# ME433Schematic.net
KiCad netlist of a schematic drawn in EAGLE
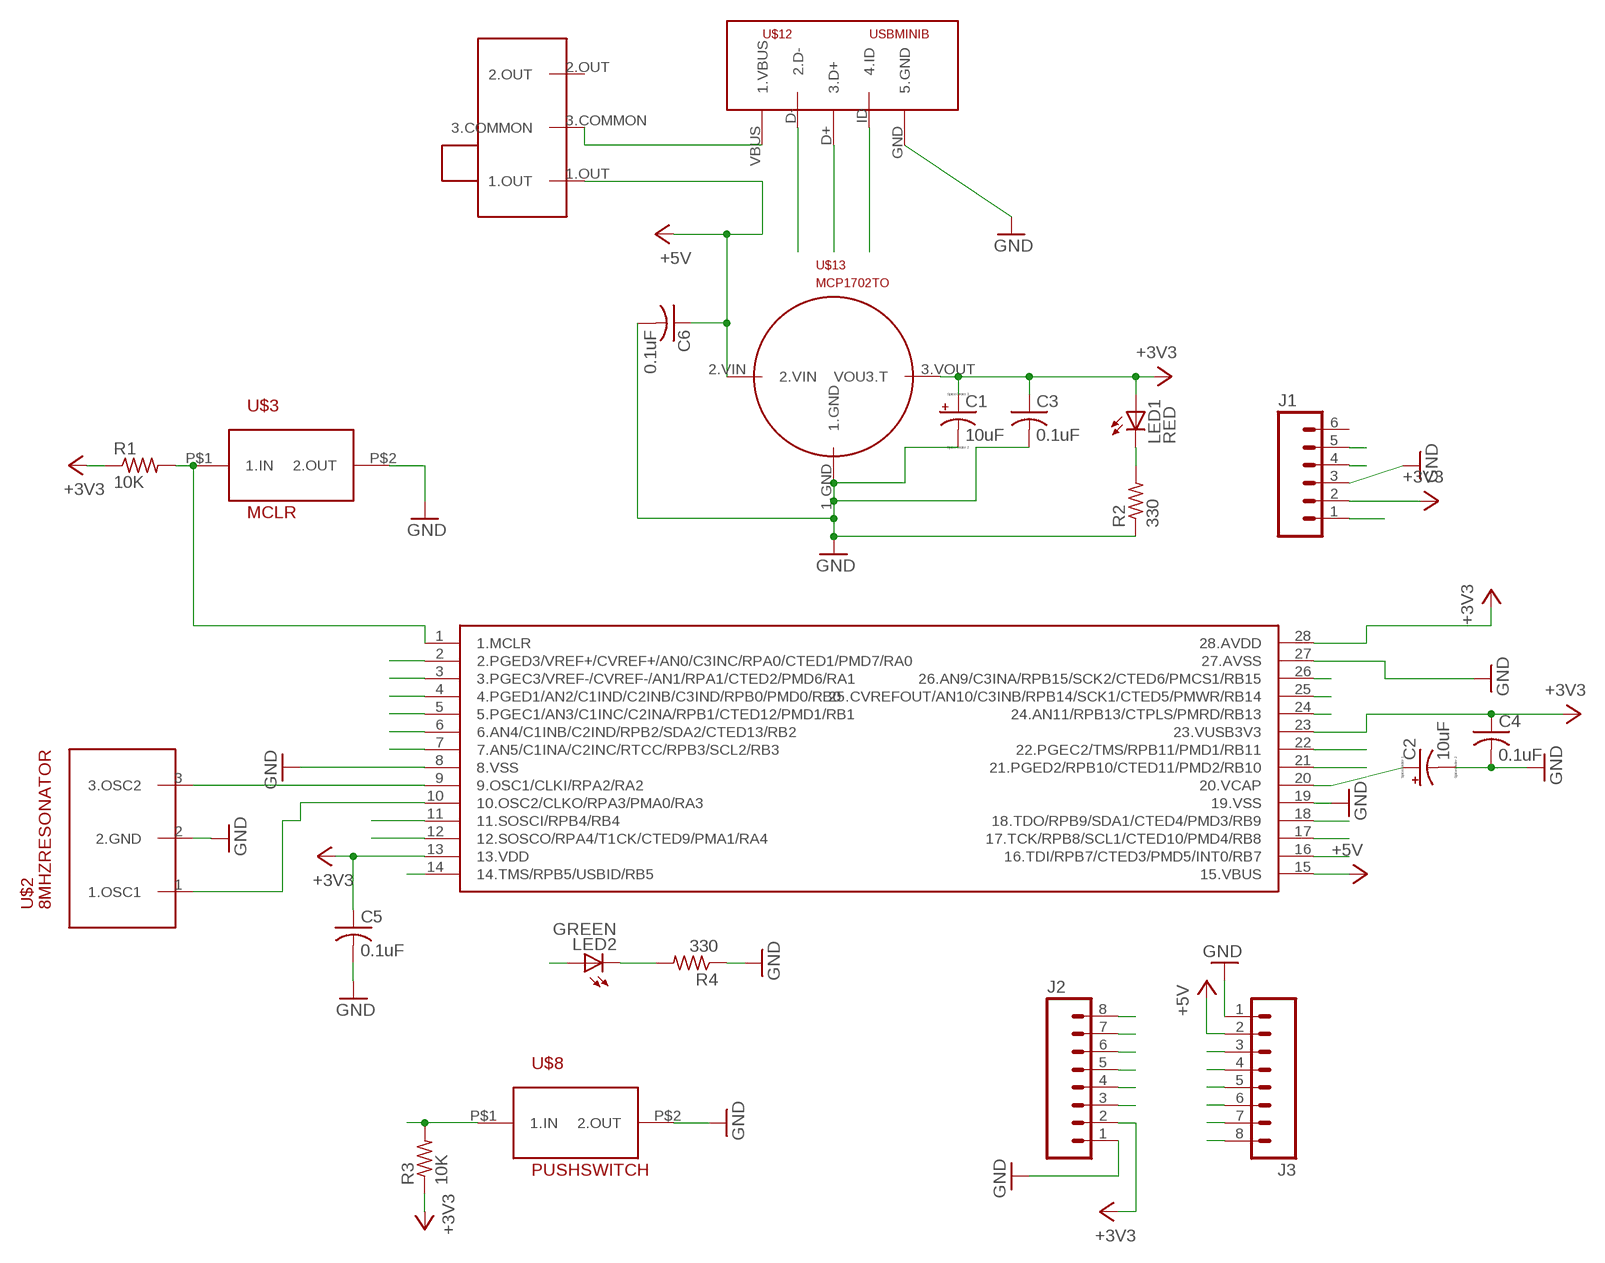
[diagram p0: schematic, sheet 1]

(export (version "E")
  (design (tool "Eeschema 10.0.6"))
  (components
    (comp (ref "C1")
      (value "10uF")
      (footprint "eagle-import:B45181B")
      (libsource (lib "eagle-import") (part "CPOL-USB45181B"))
    )
    (comp (ref "C2")
      (value "10uF")
      (footprint "eagle-import:B45181B")
      (libsource (lib "eagle-import") (part "CPOL-USB45181B"))
    )
    (comp (ref "C3")
      (value "0.1uF")
      (footprint "eagle-import:C025-025X050")
      (libsource (lib "eagle-import") (part "C-US025-025X050"))
    )
    (comp (ref "C4")
      (value "0.1uF")
      (footprint "eagle-import:C025-025X050")
      (libsource (lib "eagle-import") (part "C-US025-025X050"))
    )
    (comp (ref "C5")
      (value "0.1uF")
      (footprint "eagle-import:C025-025X050")
      (libsource (lib "eagle-import") (part "C-US025-025X050"))
    )
    (comp (ref "C6")
      (value "0.1uF")
      (footprint "eagle-import:C025-025X050")
      (libsource (lib "eagle-import") (part "C-US025-025X050"))
    )
    (comp (ref "J1")
      (value "M06SILK_FEMALE_PTH")
      (footprint "eagle-import:1X06")
      (libsource (lib "eagle-import") (part "M06SILK_FEMALE_PTH"))
    )
    (comp (ref "J2")
      (value "M08")
      (footprint "eagle-import:1X08_ROUND")
      (libsource (lib "eagle-import") (part "M08"))
    )
    (comp (ref "J3")
      (value "M08")
      (footprint "eagle-import:1X08_ROUND")
      (libsource (lib "eagle-import") (part "M08"))
    )
    (comp (ref "LED1")
      (value "RED")
      (footprint "eagle-import:LED3MM")
      (libsource (lib "eagle-import") (part "LED3MM"))
    )
    (comp (ref "LED2")
      (value "GREEN")
      (footprint "eagle-import:LED3MM")
      (libsource (lib "eagle-import") (part "LED3MM"))
    )
    (comp (ref "R1")
      (value "10K")
      (footprint "eagle-import:0207_10")
      (libsource (lib "eagle-import") (part "R-US_0207/10"))
    )
    (comp (ref "R2")
      (value "330")
      (footprint "eagle-import:0207_10")
      (libsource (lib "eagle-import") (part "R-US_0207/10"))
    )
    (comp (ref "R3")
      (value "10K")
      (footprint "eagle-import:0207_10")
      (libsource (lib "eagle-import") (part "R-US_0207/10"))
    )
    (comp (ref "R4")
      (value "330")
      (footprint "eagle-import:0207_10")
      (libsource (lib "eagle-import") (part "R-US_0207/10"))
    )
    (comp (ref "U$1")
      (value "PIC32MX250F128B")
      (footprint "eagle-import:DIL28-3")
      (libsource (lib "eagle-import") (part "PIC32MX250F128B"))
    )
    (comp (ref "U$2")
      (value "8MHZRESONATOR")
      (footprint "eagle-import:1X03")
      (libsource (lib "eagle-import") (part "8MHZRESONATOR"))
    )
    (comp (ref "U$3")
      (value "MCLR")
      (footprint "eagle-import:SWITCH")
      (libsource (lib "eagle-import") (part "PUSHSWITCH"))
    )
    (comp (ref "U$8")
      (value "PUSHSWITCH")
      (footprint "eagle-import:SWITCH")
      (libsource (lib "eagle-import") (part "PUSHSWITCH"))
    )
    (comp (ref "U$12")
      (value "USBMINIB")
      (footprint "eagle-import:USB-MB-H")
      (libsource (lib "eagle-import") (part "USBMINIB"))
    )
    (comp (ref "U$13")
      (value "MCP1702TO")
      (footprint "eagle-import:TO92")
      (libsource (lib "eagle-import") (part "MCP1702TO"))
    )
    (comp (ref "U$18")
      (value "SLIDESWITCH")
      (footprint "eagle-import:SPDTSLIDE")
      (libsource (lib "eagle-import") (part "SLIDESWITCH"))
    )
  )
  (nets
    (net (code "1") (name "+3V3") (class "Default")
      (node (ref "C1") (pin "+") (pinfunction "+_+") (pintype "passive"))
      (node (ref "C3") (pin "1") (pinfunction "1_1") (pintype "passive"))
      (node (ref "C4") (pin "1") (pinfunction "1_1") (pintype "passive"))
      (node (ref "C5") (pin "1") (pinfunction "1_1") (pintype "passive"))
      (node (ref "J1") (pin "2") (pinfunction "2_2") (pintype "passive"))
      (node (ref "J2") (pin "2") (pinfunction "2_2") (pintype "passive"))
      (node (ref "LED1") (pin "A") (pinfunction "1.+_A") (pintype "passive"))
      (node (ref "R1") (pin "1") (pinfunction "1_1") (pintype "passive"))
      (node (ref "R3") (pin "1") (pinfunction "1_1") (pintype "passive"))
      (node (ref "U$1") (pin "13") (pinfunction "13.VDD_13") (pintype "bidirectional"))
      (node (ref "U$1") (pin "23") (pinfunction "23.VUSB3V3_23") (pintype "bidirectional"))
      (node (ref "U$1") (pin "28") (pinfunction "28.AVDD_28") (pintype "bidirectional"))
      (node (ref "U$13") (pin "3.VOUT") (pinfunction "VOU3.T_3.VOUT") (pintype "bidirectional"))
    )
    (net (code "2") (name "+5V") (class "Default")
      (node (ref "C6") (pin "1") (pinfunction "1_1") (pintype "passive"))
      (node (ref "J3") (pin "2") (pinfunction "2_2") (pintype "passive"))
      (node (ref "U$1") (pin "15") (pinfunction "15.VBUS_15") (pintype "bidirectional"))
      (node (ref "U$13") (pin "2.VIN") (pinfunction "2.VIN_2.VIN") (pintype "bidirectional"))
      (node (ref "U$18") (pin "1.OUT") (pinfunction "1.OUT_1.OUT") (pintype "bidirectional"))
    )
    (net (code "3") (name "/A0") (class "Default")
      (node (ref "J2") (pin "8") (pinfunction "8_8") (pintype "passive"))
      (node (ref "U$1") (pin "2") (pinfunction "2.PGED3/VREF+/CVREF+/AN0/C3INC/RPA0/CTED1/PMD7/RA0_2") (pintype "bidirectional"))
    )
    (net (code "4") (name "/A1") (class "Default")
      (node (ref "J2") (pin "7") (pinfunction "7_7") (pintype "passive"))
      (node (ref "U$1") (pin "3") (pinfunction "3.PGEC3/VREF-/CVREF-/AN1/RPA1/CTED2/PMD6/RA1_3") (pintype "bidirectional"))
    )
    (net (code "5") (name "/A4") (class "Default")
      (node (ref "J2") (pin "3") (pinfunction "3_3") (pintype "passive"))
      (node (ref "LED2") (pin "A") (pinfunction "1.+_A") (pintype "passive"))
      (node (ref "U$1") (pin "12") (pinfunction "12.SOSCO/RPA4/T1CK/CTED9/PMA1/RA4_12") (pintype "bidirectional"))
    )
    (net (code "6") (name "/B2") (class "Default")
      (node (ref "J2") (pin "6") (pinfunction "6_6") (pintype "passive"))
      (node (ref "U$1") (pin "6") (pinfunction "6.AN4/C1INB/C2IND/RPB2/SDA2/CTED13/RB2_6") (pintype "bidirectional"))
    )
    (net (code "7") (name "/B3") (class "Default")
      (node (ref "J2") (pin "5") (pinfunction "5_5") (pintype "passive"))
      (node (ref "U$1") (pin "7") (pinfunction "7.AN5/C1INA/C2INC/RTCC/RPB3/SCL2/RB3_7") (pintype "bidirectional"))
    )
    (net (code "8") (name "/B4") (class "Default")
      (node (ref "J2") (pin "4") (pinfunction "4_4") (pintype "passive"))
      (node (ref "R3") (pin "2") (pinfunction "2_2") (pintype "passive"))
      (node (ref "U$1") (pin "11") (pinfunction "11.SOSCI/RPB4/RB4_11") (pintype "bidirectional"))
      (node (ref "U$8") (pin "P$1") (pinfunction "1.IN_P$1") (pintype "bidirectional"))
    )
    (net (code "9") (name "/B7") (class "Default")
      (node (ref "J3") (pin "3") (pinfunction "3_3") (pintype "passive"))
      (node (ref "U$1") (pin "16") (pinfunction "16.TDI/RPB7/CTED3/PMD5/INT0/RB7_16") (pintype "bidirectional"))
    )
    (net (code "10") (name "/B8") (class "Default")
      (node (ref "J3") (pin "4") (pinfunction "4_4") (pintype "passive"))
      (node (ref "U$1") (pin "17") (pinfunction "17.TCK/RPB8/SCL1/CTED10/PMD4/RB8_17") (pintype "bidirectional"))
    )
    (net (code "11") (name "/B9") (class "Default")
      (node (ref "J3") (pin "5") (pinfunction "5_5") (pintype "passive"))
      (node (ref "U$1") (pin "18") (pinfunction "18.TDO/RPB9/SDA1/CTED4/PMD3/RB9_18") (pintype "bidirectional"))
    )
    (net (code "12") (name "/B13") (class "Default")
      (node (ref "J3") (pin "6") (pinfunction "6_6") (pintype "passive"))
      (node (ref "U$1") (pin "24") (pinfunction "24.AN11/RPB13/CTPLS/PMRD/RB13_24") (pintype "bidirectional"))
    )
    (net (code "13") (name "/B14") (class "Default")
      (node (ref "J3") (pin "7") (pinfunction "7_7") (pintype "passive"))
      (node (ref "U$1") (pin "25") (pinfunction "25.CVREFOUT/AN10/C3INB/RPB14/SCK1/CTED5/PMWR/RB14_25") (pintype "bidirectional"))
    )
    (net (code "14") (name "/B15") (class "Default")
      (node (ref "J3") (pin "8") (pinfunction "8_8") (pintype "passive"))
      (node (ref "U$1") (pin "26") (pinfunction "26.AN9/C3INA/RPB15/SCK2/CTED6/PMCS1/RB15_26") (pintype "bidirectional"))
    )
    (net (code "15") (name "/D+") (class "Default")
      (node (ref "U$1") (pin "21") (pinfunction "21.PGED2/RPB10/CTED11/PMD2/RB10_21") (pintype "bidirectional"))
      (node (ref "U$12") (pin "D+") (pinfunction "3.D+_D+") (pintype "bidirectional"))
    )
    (net (code "16") (name "/D-") (class "Default")
      (node (ref "U$1") (pin "22") (pinfunction "22.PGEC2/TMS/RPB11/PMD1/RB11_22") (pintype "bidirectional"))
      (node (ref "U$12") (pin "D-") (pinfunction "2.D-_D-") (pintype "bidirectional"))
    )
    (net (code "17") (name "/ID") (class "Default")
      (node (ref "U$1") (pin "14") (pinfunction "14.TMS/RPB5/USBID/RB5_14") (pintype "bidirectional"))
      (node (ref "U$12") (pin "ID") (pinfunction "4.ID_ID") (pintype "bidirectional"))
    )
    (net (code "18") (name "/MCLR") (class "Default")
      (node (ref "J1") (pin "1") (pinfunction "1_1") (pintype "passive"))
      (node (ref "R1") (pin "2") (pinfunction "2_2") (pintype "passive"))
      (node (ref "U$1") (pin "1") (pinfunction "1.MCLR_1") (pintype "bidirectional"))
      (node (ref "U$3") (pin "P$1") (pinfunction "1.IN_P$1") (pintype "bidirectional"))
    )
    (net (code "19") (name "/PEGC1") (class "Default")
      (node (ref "J1") (pin "5") (pinfunction "5_5") (pintype "passive"))
      (node (ref "U$1") (pin "5") (pinfunction "5.PGEC1/AN3/C1INC/C2INA/RPB1/CTED12/PMD1/RB1_5") (pintype "bidirectional"))
    )
    (net (code "20") (name "/PEGD1") (class "Default")
      (node (ref "J1") (pin "4") (pinfunction "4_4") (pintype "passive"))
      (node (ref "U$1") (pin "4") (pinfunction "4.PGED1/AN2/C1IND/C2INB/C3IND/RPB0/PMD0/RB0_4") (pintype "bidirectional"))
    )
    (net (code "21") (name "GND") (class "Default")
      (node (ref "C1") (pin "-") (pinfunction "-_-") (pintype "passive"))
      (node (ref "C2") (pin "-") (pinfunction "-_-") (pintype "passive"))
      (node (ref "C3") (pin "2") (pinfunction "2_2") (pintype "passive"))
      (node (ref "C4") (pin "2") (pinfunction "2_2") (pintype "passive"))
      (node (ref "C5") (pin "2") (pinfunction "2_2") (pintype "passive"))
      (node (ref "C6") (pin "2") (pinfunction "2_2") (pintype "passive"))
      (node (ref "J1") (pin "3") (pinfunction "3_3") (pintype "passive"))
      (node (ref "J2") (pin "1") (pinfunction "1_1") (pintype "passive"))
      (node (ref "J3") (pin "1") (pinfunction "1_1") (pintype "passive"))
      (node (ref "R2") (pin "1") (pinfunction "1_1") (pintype "passive"))
      (node (ref "R4") (pin "1") (pinfunction "1_1") (pintype "passive"))
      (node (ref "U$1") (pin "19") (pinfunction "19.VSS_19") (pintype "bidirectional"))
      (node (ref "U$1") (pin "27") (pinfunction "27.AVSS_27") (pintype "bidirectional"))
      (node (ref "U$1") (pin "8") (pinfunction "8.VSS_8") (pintype "bidirectional"))
      (node (ref "U$12") (pin "GND") (pinfunction "5.GND_GND") (pintype "bidirectional"))
      (node (ref "U$13") (pin "1.GND") (pinfunction "1.GND_1.GND") (pintype "bidirectional"))
      (node (ref "U$2") (pin "2") (pinfunction "2.GND_2") (pintype "bidirectional"))
      (node (ref "U$3") (pin "P$2") (pinfunction "2.OUT_P$2") (pintype "bidirectional"))
      (node (ref "U$8") (pin "P$2") (pinfunction "2.OUT_P$2") (pintype "bidirectional"))
    )
    (net (code "22") (name "Net-(LED1-2.-)") (class "Default")
      (node (ref "LED1") (pin "K") (pinfunction "2.-_K") (pintype "passive"))
      (node (ref "R2") (pin "2") (pinfunction "2_2") (pintype "passive"))
    )
    (net (code "23") (name "Net-(LED2-2.-)") (class "Default")
      (node (ref "LED2") (pin "K") (pinfunction "2.-_K") (pintype "passive"))
      (node (ref "R4") (pin "2") (pinfunction "2_2") (pintype "passive"))
    )
    (net (code "24") (name "Net-(U$1-9.OSC1{slash}CLKI{slash}RPA2{slash}RA2)") (class "Default")
      (node (ref "U$1") (pin "9") (pinfunction "9.OSC1/CLKI/RPA2/RA2_9") (pintype "bidirectional"))
      (node (ref "U$2") (pin "3") (pinfunction "3.OSC2_3") (pintype "bidirectional"))
    )
    (net (code "25") (name "Net-(U$1-10.OSC2{slash}CLKO{slash}RPA3{slash}PMA0{slash}RA3)") (class "Default")
      (node (ref "U$1") (pin "10") (pinfunction "10.OSC2/CLKO/RPA3/PMA0/RA3_10") (pintype "bidirectional"))
      (node (ref "U$2") (pin "1") (pinfunction "1.OSC1_1") (pintype "bidirectional"))
    )
    (net (code "26") (name "Net-(U$1-20.VCAP)") (class "Default")
      (node (ref "C2") (pin "+") (pinfunction "+_+") (pintype "passive"))
      (node (ref "U$1") (pin "20") (pinfunction "20.VCAP_20") (pintype "bidirectional"))
    )
    (net (code "27") (name "Net-(U$12-1.VBUS)") (class "Default")
      (node (ref "U$12") (pin "VBUS") (pinfunction "1.VBUS_VBUS") (pintype "bidirectional"))
      (node (ref "U$18") (pin "3.COMMON") (pinfunction "3.COMMON_3.COMMON") (pintype "bidirectional"))
    )
    (net (code "28") (name "unconnected-(J1-Pad6)") (class "Default")
      (node (ref "J1") (pin "6") (pinfunction "6_6") (pintype "passive"))
    )
    (net (code "29") (name "unconnected-(U$18-Pad2.OUT)") (class "Default")
      (node (ref "U$18") (pin "2.OUT") (pinfunction "2.OUT_2.OUT") (pintype "bidirectional"))
    )
  )
)
